# improved-handheld-turbidimeter_DAC_LED.net
KiCad netlist of a schematic drawn in EAGLE
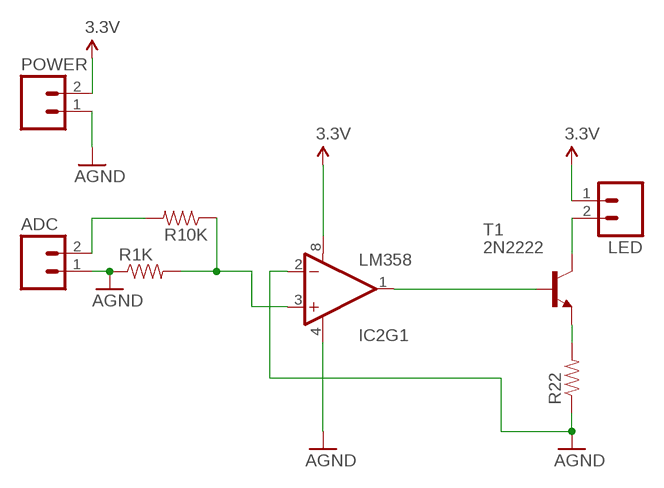
[diagram p0: schematic, sheet 1]

(export (version "E")
  (design (tool "Eeschema 10.0.6"))
  (components
    (comp (ref "ADC")
      (value "M02PTH")
      (footprint "eagle-import:1X02")
      (libsource (lib "eagle-import") (part "M02PTH"))
    )
    (comp (ref "IC2")
      (value "LM358")
      (footprint "eagle-import:DIP08")
      (libsource (lib "eagle-import") (part "LM358"))
    )
    (comp (ref "LED")
      (value "M02PTH")
      (footprint "eagle-import:1X02")
      (libsource (lib "eagle-import") (part "M02PTH"))
    )
    (comp (ref "POWER")
      (value "M02PTH")
      (footprint "eagle-import:1X02")
      (libsource (lib "eagle-import") (part "M02PTH"))
    )
    (comp (ref "R1K")
      (value "RESISTOR0603-RES")
      (footprint "eagle-import:0603-RES")
      (libsource (lib "eagle-import") (part "RESISTOR0603-RES"))
    )
    (comp (ref "R10K")
      (value "RESISTOR0603-RES")
      (footprint "eagle-import:0603-RES")
      (libsource (lib "eagle-import") (part "RESISTOR0603-RES"))
    )
    (comp (ref "R22")
      (value "RESISTOR0603-RES")
      (footprint "eagle-import:0603-RES")
      (libsource (lib "eagle-import") (part "RESISTOR0603-RES"))
    )
    (comp (ref "T1")
      (value "2N2222")
      (footprint "eagle-import:TO92-EBC-OVAL")
      (libsource (lib "eagle-import") (part "2N2222"))
    )
  )
  (nets
    (net (code "1") (name "3.3V") (class "Default")
      (node (ref "IC2") (pin "8") (pinfunction "V+_8") (pintype "power_in"))
      (node (ref "LED") (pin "1") (pinfunction "1_1") (pintype "passive"))
      (node (ref "POWER") (pin "2") (pinfunction "2_2") (pintype "passive"))
    )
    (net (code "2") (name "AGND") (class "Default")
      (node (ref "ADC") (pin "1") (pinfunction "1_1") (pintype "passive"))
      (node (ref "IC2") (pin "2") (pinfunction "-IN_2") (pintype "input"))
      (node (ref "IC2") (pin "4") (pinfunction "V-_4") (pintype "power_in"))
      (node (ref "POWER") (pin "1") (pinfunction "1_1") (pintype "passive"))
      (node (ref "R1K") (pin "1") (pinfunction "1_1") (pintype "passive"))
      (node (ref "R22") (pin "1") (pinfunction "1_1") (pintype "passive"))
    )
    (net (code "3") (name "Net-(ADC-Pad2)") (class "Default")
      (node (ref "ADC") (pin "2") (pinfunction "2_2") (pintype "passive"))
      (node (ref "R10K") (pin "2") (pinfunction "2_2") (pintype "passive"))
    )
    (net (code "4") (name "Net-(IC2A-+IN)") (class "Default")
      (node (ref "IC2") (pin "3") (pinfunction "+IN_3") (pintype "input"))
      (node (ref "R10K") (pin "1") (pinfunction "1_1") (pintype "passive"))
      (node (ref "R1K") (pin "2") (pinfunction "2_2") (pintype "passive"))
    )
    (net (code "5") (name "Net-(IC2A-OUT)") (class "Default")
      (node (ref "IC2") (pin "1") (pinfunction "OUT_1") (pintype "output"))
      (node (ref "T1") (pin "B") (pinfunction "B_B") (pintype "passive"))
    )
    (net (code "6") (name "Net-(LED-Pad2)") (class "Default")
      (node (ref "LED") (pin "2") (pinfunction "2_2") (pintype "passive"))
      (node (ref "T1") (pin "C") (pinfunction "C_C") (pintype "passive"))
    )
    (net (code "7") (name "Net-(R22-Pad2)") (class "Default")
      (node (ref "R22") (pin "2") (pinfunction "2_2") (pintype "passive"))
      (node (ref "T1") (pin "E") (pinfunction "E_E") (pintype "passive"))
    )
  )
)
